# SUP_2_5_FMC.net
KiCad netlist of a schematic drawn in Altium Designer
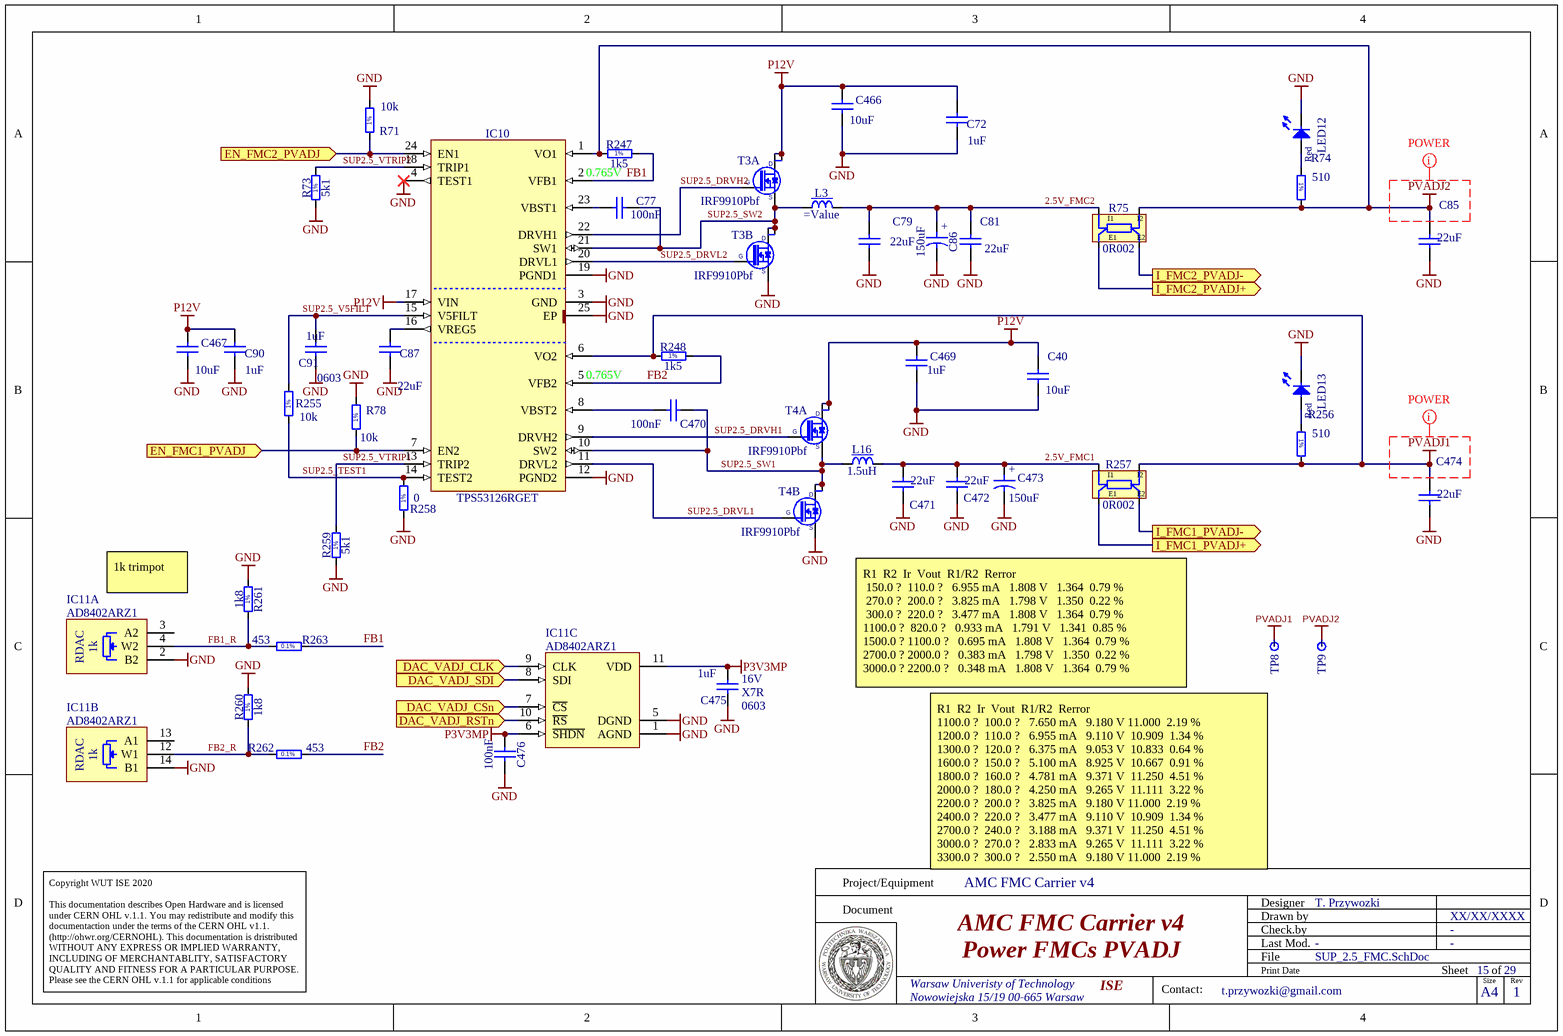
[diagram p0: SUP_2.5_FMC.SchDoc]

(export (version "E")
  (design (tool "Eeschema 10.0.6"))
  (components
    (comp (ref "C40")
      (value "10uF")
      (footprint "CAPC2012X135N")
      (description "Non-polarised capacitor")
      (fields
        (field (name "PART NUMBER") "CC0805_10UF_16V_10%_X5R")
        (field (name "VOLTAGE") "16V")
        (field (name "AUTHOR") "CERN DEM JLC")
      )
      (libsource (lib "Capacitors") (part "Capacitor - non polarized"))
    )
    (comp (ref "C72")
      (value "1uF")
      (footprint "CAPC1608X87N")
      (description "Non-polarised capacitor")
      (fields
        (field (name "PART NUMBER") "CC0603_1UF_16V_10%_X7R")
        (field (name "VOLTAGE") "16V")
        (field (name "AUTHOR") "CERN DEM JLC")
      )
      (libsource (lib "Capacitors") (part "Capacitor - non polarized"))
    )
    (comp (ref "C77")
      (value "100nF")
      (footprint "CAPC1005X55N")
      (description "Non-polarised capacitor")
      (fields
        (field (name "PART NUMBER") "CC0402_100NF_16V_10%_X7R")
        (field (name "VOLTAGE") "16V")
        (field (name "AUTHOR") "CERN DEM JLC")
      )
      (libsource (lib "Capacitors") (part "Capacitor - non polarized"))
    )
    (comp (ref "C79")
      (value "22uF")
      (footprint "CAPC3216X180N")
      (description "Non-polarised capacitor")
      (fields
        (field (name "PART NUMBER") "CC1206_22UF_10V_10%_X7R")
        (field (name "VOLTAGE") "10V")
        (field (name "AUTHOR") "CERN DEM JLC")
      )
      (libsource (lib "Capacitors") (part "Capacitor - non polarized"))
    )
    (comp (ref "C81")
      (value "22uF")
      (footprint "CAPC3216X180N")
      (description "Non-polarised capacitor")
      (fields
        (field (name "PART NUMBER") "CC1206_22UF_10V_10%_X7R")
        (field (name "VOLTAGE") "10V")
        (field (name "AUTHOR") "CERN DEM JLC")
      )
      (libsource (lib "Capacitors") (part "Capacitor - non polarized"))
    )
    (comp (ref "C85")
      (value "22uF")
      (footprint "CAPC3216X180N")
      (description "Non-polarised capacitor")
      (fields
        (field (name "PART NUMBER") "CC1206_22UF_10V_10%_X7R")
        (field (name "VOLTAGE") "10V")
        (field (name "AUTHOR") "CERN DEM JLC")
      )
      (libsource (lib "Capacitors") (part "Capacitor - non polarized"))
    )
    (comp (ref "C86")
      (value "150uF")
      (footprint "CAPMP7343X200N")
      (description "Polarised capacitor")
      (fields
        (field (name "PART NUMBER") "CAEM7343-20_150UF_4V_20%_LESR0016")
        (field (name "VOLTAGE") "4V")
        (field (name "AUTHOR") "CERN DEM JLC")
      )
      (libsource (lib "Capacitors") (part "Capacitor - polarized"))
    )
    (comp (ref "C87")
      (value "22uF")
      (footprint "CAPC3216X180N")
      (description "Non-polarised capacitor")
      (fields
        (field (name "PART NUMBER") "CC1206_22UF_10V_10%_X7R")
        (field (name "VOLTAGE") "10V")
        (field (name "AUTHOR") "CERN DEM JLC")
      )
      (libsource (lib "Capacitors") (part "Capacitor - non polarized"))
    )
    (comp (ref "C90")
      (value "1uF")
      (footprint "CAPC1608X87N")
      (description "Non-polarised capacitor")
      (fields
        (field (name "PART NUMBER") "CC0603_1UF_16V_10%_X7R")
        (field (name "VOLTAGE") "16V")
        (field (name "AUTHOR") "CERN DEM JLC")
      )
      (libsource (lib "Capacitors") (part "Capacitor - non polarized"))
    )
    (comp (ref "C91")
      (value "1uF")
      (footprint "CAPC1608X87N")
      (description "Non-polarised capacitor")
      (fields
        (field (name "PART NUMBER") "CC0603_1UF_16V_10%_X7R")
        (field (name "VOLTAGE") "16V")
        (field (name "CASE") "0603")
        (field (name "AUTHOR") "CERN DEM JLC")
      )
      (libsource (lib "Capacitors") (part "Capacitor - non polarized"))
    )
    (comp (ref "C466")
      (value "10uF")
      (footprint "CAPC2012X135N")
      (description "Non-polarised capacitor")
      (fields
        (field (name "PART NUMBER") "CC0805_10UF_16V_10%_X5R")
        (field (name "VOLTAGE") "16V")
        (field (name "AUTHOR") "CERN DEM JLC")
      )
      (libsource (lib "Capacitors") (part "Capacitor - non polarized"))
    )
    (comp (ref "C467")
      (value "10uF")
      (footprint "CAPC2012X135N")
      (description "Non-polarised capacitor")
      (fields
        (field (name "PART NUMBER") "CC0805_10UF_16V_10%_X5R")
        (field (name "VOLTAGE") "16V")
        (field (name "AUTHOR") "CERN DEM JLC")
      )
      (libsource (lib "Capacitors") (part "Capacitor - non polarized"))
    )
    (comp (ref "C469")
      (value "1uF")
      (footprint "CAPC1608X87N")
      (description "Non-polarised capacitor")
      (fields
        (field (name "PART NUMBER") "CC0603_1UF_16V_10%_X7R")
        (field (name "VOLTAGE") "16V")
        (field (name "AUTHOR") "CERN DEM JLC")
      )
      (libsource (lib "Capacitors") (part "Capacitor - non polarized"))
    )
    (comp (ref "C470")
      (value "100nF")
      (footprint "CAPC1005X55N")
      (description "Non-polarised capacitor")
      (fields
        (field (name "PART NUMBER") "CC0402_100NF_16V_10%_X7R")
        (field (name "VOLTAGE") "16V")
        (field (name "AUTHOR") "CERN DEM JLC")
      )
      (libsource (lib "Capacitors") (part "Capacitor - non polarized"))
    )
    (comp (ref "C471")
      (value "22uF")
      (footprint "CAPC3216X180N")
      (description "Non-polarised capacitor")
      (fields
        (field (name "PART NUMBER") "CC1206_22UF_10V_10%_X7R")
        (field (name "VOLTAGE") "10V")
        (field (name "AUTHOR") "CERN DEM JLC")
      )
      (libsource (lib "Capacitors") (part "Capacitor - non polarized"))
    )
    (comp (ref "C472")
      (value "22uF")
      (footprint "CAPC3216X180N")
      (description "Non-polarised capacitor")
      (fields
        (field (name "PART NUMBER") "CC1206_22UF_10V_10%_X7R")
        (field (name "VOLTAGE") "10V")
        (field (name "AUTHOR") "CERN DEM JLC")
      )
      (libsource (lib "Capacitors") (part "Capacitor - non polarized"))
    )
    (comp (ref "C473")
      (value "150uF")
      (footprint "CAPMP7343X200N")
      (description "Polarised capacitor")
      (fields
        (field (name "PART NUMBER") "CAEM7343-20_150UF_4V_20%_LESR0016")
        (field (name "VOLTAGE") "4V")
        (field (name "AUTHOR") "CERN DEM JLC")
      )
      (libsource (lib "Capacitors") (part "Capacitor - polarized"))
    )
    (comp (ref "C474")
      (value "22uF")
      (footprint "CAPC3216X180N")
      (description "Non-polarised capacitor")
      (fields
        (field (name "PART NUMBER") "CC1206_22UF_10V_10%_X7R")
        (field (name "VOLTAGE") "10V")
        (field (name "AUTHOR") "CERN DEM JLC")
      )
      (libsource (lib "Capacitors") (part "Capacitor - non polarized"))
    )
    (comp (ref "C475")
      (value "1uF")
      (footprint "CAPC1608X87N")
      (description "Non-polarised capacitor")
      (fields
        (field (name "PART NUMBER") "CC0603_1UF_16V_10%_X7R")
        (field (name "VOLTAGE") "16V")
        (field (name "TC") "X7R")
        (field (name "TOLERANCE") "±10%")
        (field (name "CASE") "0603")
        (field (name "AUTHOR") "CERN DEM JLC")
      )
      (libsource (lib "Capacitors") (part "Capacitor - non polarized"))
    )
    (comp (ref "C476")
      (value "100nF")
      (footprint "CAPC0603X33N")
      (description "Non-polarised capacitor")
      (fields
        (field (name "PART NUMBER") "CC0201_100NF_6.3V_10%_X5R")
        (field (name "VOLTAGE") "6.3V")
        (field (name "AUTHOR") "CERN DEM JLC")
      )
      (libsource (lib "Capacitors") (part "Capacitor - non polarized"))
    )
    (comp (ref "IC10")
      (value "TPS53126RGET")
      (footprint "QFN50P400X400X100-25N-S255")
      (description "Dual Synchronous Step-Down Controller For Low Voltage Power Rails")
      (fields (field (name "MANUFACTURER") "TEXAS INSTRUMENTS") (field (name "AUTHOR") "CERN DEM JLC"))
      (libsource (lib "ICs And Semiconductors") (part "TPS53126RGET"))
    )
    (comp (ref "IC11")
      (value "AD8402ARZ1")
      (footprint "SOIC127P600X175-14N")
      (description "2-Channel 1k Digital Potentiometer")
      (fields (field (name "MANUFACTURER") "ANALOG DEVICES") (field (name "AUTHOR") "CERN DEM JLC"))
      (libsource (lib "ICs And Semiconductors") (part "AD8402ARZ1"))
    )
    (comp (ref "L3")
      (value "~")
      (description "Inductor With Core")
      (libsource (lib "altium-import") (part "root_0_Inductor With Magnetic core_"))
    )
    (comp (ref "L16")
      (value "1.5uH")
      (footprint "IND_TDK_SPM6530")
      (description "Inductor With Core")
      (fields
        (field (name "PART NUMBER") "IND_1.5UH_20%_TDK_SPM6530")
        (field (name "POWER") "11A")
        (field (name "AUTHOR") "CERN DEM MR")
      )
      (libsource (lib "Inductors & Transformers") (part "Inductor With Magnetic core"))
    )
    (comp (ref "LED12")
      (value "Red")
      (footprint "LED_KINGBRIGHT_KPH-1608SURCK")
      (description "LED Red 1C 2A")
      (fields
        (field (name "PART NUMBER") "LED_KINGBRIGHT_KPH-1608SURCK")
        (field (name "MANUFACTURER") "KINGBRIGHT")
        (field (name "AUTHOR") "CERN DEM JLC")
      )
      (libsource (lib "ICs And Semiconductors") (part "LED Red 1C 2A"))
    )
    (comp (ref "LED13")
      (value "Red")
      (footprint "LED_KINGBRIGHT_KPH-1608SURCK")
      (description "LED Red 1C 2A")
      (fields
        (field (name "PART NUMBER") "LED_KINGBRIGHT_KPH-1608SURCK")
        (field (name "MANUFACTURER") "KINGBRIGHT")
        (field (name "AUTHOR") "CERN DEM JLC")
      )
      (libsource (lib "ICs And Semiconductors") (part "LED Red 1C 2A"))
    )
    (comp (ref "R71")
      (value "10k")
      (footprint "RESC1005X40N")
      (description "Resistor - 1%")
      (fields
        (field (name "PART NUMBER") "R0402_10K_1%_0.0625W_100PPM")
        (field (name "POWER") "0.0625W")
        (field (name "AUTHOR") "CERN DEM JLC")
      )
      (libsource (lib "Resistors") (part "Resistor - 1%"))
    )
    (comp (ref "R73")
      (value "5k1")
      (footprint "RESC1608X55N")
      (description "Resistor - 1%")
      (fields
        (field (name "PART NUMBER") "R0603_5K1_1%_0.1W_100PPM")
        (field (name "POWER") "0.1W")
        (field (name "AUTHOR") "CERN DEM JLC")
      )
      (libsource (lib "Resistors") (part "Resistor - 1%"))
    )
    (comp (ref "R74")
      (value "510")
      (footprint "RESC1005X40N")
      (description "Resistor - 1%")
      (fields
        (field (name "PART NUMBER") "R0402_510R_1%_0.0625W_100PPM")
        (field (name "POWER") "0.0625W")
        (field (name "AUTHOR") "CERN DEM JLC")
      )
      (libsource (lib "Resistors") (part "Resistor - 1%"))
    )
    (comp (ref "R75")
      (value "0R002")
      (footprint "RES_VISHAY_WSK2512_0R005-0R2")
      (description "Power and Current Sensing Resistor")
      (fields
        (field (name "PART NUMBER") "R2512_0R002_1%_1W_35PPM_VISHAY_WSK")
        (field (name "POWER") "1W")
        (field (name "AUTHOR") "CERN DEM MR")
      )
      (libsource (lib "Resistors") (part "Current Sense Resistor"))
    )
    (comp (ref "R78")
      (value "10k")
      (footprint "RESC1005X40N")
      (description "Resistor - 1%")
      (fields
        (field (name "PART NUMBER") "R0402_10K_1%_0.0625W_100PPM")
        (field (name "POWER") "0.0625W")
        (field (name "AUTHOR") "CERN DEM JLC")
      )
      (libsource (lib "Resistors") (part "Resistor - 1%"))
    )
    (comp (ref "R247")
      (value "1k5")
      (footprint "RESC1608X55N")
      (description "Resistor - 1%")
      (fields
        (field (name "PART NUMBER") "R0603_1K5_1%_0.1W_100PPM")
        (field (name "POWER") "0.1W")
        (field (name "AUTHOR") "CERN DEM JLC")
      )
      (libsource (lib "Resistors") (part "Resistor - 1%"))
    )
    (comp (ref "R248")
      (value "1k5")
      (footprint "RESC1608X55N")
      (description "Resistor - 1%")
      (fields
        (field (name "PART NUMBER") "R0603_1K5_1%_0.1W_100PPM")
        (field (name "POWER") "0.1W")
        (field (name "AUTHOR") "CERN DEM JLC")
      )
      (libsource (lib "Resistors") (part "Resistor - 1%"))
    )
    (comp (ref "R255")
      (value "10k")
      (footprint "RESC1005X40N")
      (description "Resistor - 1%")
      (fields
        (field (name "PART NUMBER") "R0402_10K_1%_0.0625W_100PPM")
        (field (name "POWER") "0.0625W")
        (field (name "AUTHOR") "CERN DEM JLC")
      )
      (libsource (lib "Resistors") (part "Resistor - 1%"))
    )
    (comp (ref "R256")
      (value "510")
      (footprint "RESC1005X40N")
      (description "Resistor - 1%")
      (fields
        (field (name "PART NUMBER") "R0402_510R_1%_0.0625W_100PPM")
        (field (name "POWER") "0.0625W")
        (field (name "AUTHOR") "CERN DEM JLC")
      )
      (libsource (lib "Resistors") (part "Resistor - 1%"))
    )
    (comp (ref "R257")
      (value "0R002")
      (footprint "RES_VISHAY_WSK2512_0R005-0R2")
      (description "Power and Current Sensing Resistor")
      (fields
        (field (name "PART NUMBER") "R2512_0R002_1%_1W_35PPM_VISHAY_WSK")
        (field (name "POWER") "1W")
        (field (name "AUTHOR") "CERN DEM MR")
      )
      (libsource (lib "Resistors") (part "Current Sense Resistor"))
    )
    (comp (ref "R258")
      (value "0")
      (footprint "RESC1005X40N")
      (description "Resistor - 1%")
      (fields
        (field (name "PART NUMBER") "R0402_0R_JUMPER")
        (field (name "MANUFACTURER") "GENERIC")
        (field (name "AUTHOR") "CERN DEM JLC")
      )
      (libsource (lib "Resistors") (part "Resistor - 1%"))
    )
    (comp (ref "R259")
      (value "5k1")
      (footprint "RESC1608X55N")
      (description "Resistor - 1%")
      (fields
        (field (name "PART NUMBER") "R0603_5K1_1%_0.1W_100PPM")
        (field (name "POWER") "0.1W")
        (field (name "AUTHOR") "CERN DEM JLC")
      )
      (libsource (lib "Resistors") (part "Resistor - 1%"))
    )
    (comp (ref "R260")
      (value "1k8")
      (footprint "RESC1608X55N")
      (description "Resistor - 1%")
      (fields
        (field (name "PART NUMBER") "R0603_910R_1%_0.1W_100PPM")
        (field (name "POWER") "0.1W")
        (field (name "AUTHOR") "CERN DEM JLC")
      )
      (libsource (lib "Resistors") (part "Resistor - 1%"))
    )
    (comp (ref "R261")
      (value "1k8")
      (footprint "RESC1608X55N")
      (description "Resistor - 1%")
      (fields
        (field (name "PART NUMBER") "R0603_910R_1%_0.1W_100PPM")
        (field (name "POWER") "0.1W")
        (field (name "AUTHOR") "CERN DEM JLC")
      )
      (libsource (lib "Resistors") (part "Resistor - 1%"))
    )
    (comp (ref "R262")
      (value "453")
      (footprint "RESC1608X55N")
      (description "Resistor - 0.1%")
      (fields
        (field (name "PART NUMBER") "R0603_453R_0.1%_0.063W_10PPM")
        (field (name "POWER") "0.063W")
        (field (name "AUTHOR") "CERN DEM JLC")
      )
      (libsource (lib "Resistors") (part "Resistor - 0.1%"))
    )
    (comp (ref "R263")
      (value "453")
      (footprint "RESC1608X55N")
      (description "Resistor - 0.1%")
      (fields
        (field (name "PART NUMBER") "R0603_453R_0.1%_0.063W_10PPM")
        (field (name "POWER") "0.063W")
        (field (name "AUTHOR") "CERN DEM JLC")
      )
      (libsource (lib "Resistors") (part "Resistor - 0.1%"))
    )
    (comp (ref "T3")
      (value "IRF9910Pbf")
      (footprint "SOIC127P600X175-8N")
      (description "Dual SO-8 MOSFET For POL Cconverter")
      (fields (field (name "MANUFACTURER") "INTERNATIONAL RECTIFIER") (field (name "AUTHOR") "CERN DEM JLC"))
      (libsource (lib "ICs And Semiconductors") (part "IRF9910"))
    )
    (comp (ref "T4")
      (value "IRF9910Pbf")
      (footprint "SOIC127P600X175-8N")
      (description "Dual SO-8 MOSFET For POL Cconverter")
      (fields (field (name "MANUFACTURER") "INTERNATIONAL RECTIFIER") (field (name "AUTHOR") "CERN DEM JLC"))
      (libsource (lib "ICs And Semiconductors") (part "IRF9910"))
    )
    (comp (ref "TP8")
      (value "Test Point")
      (footprint "TPS127")
      (fields (field (name "PART NUMBER") "SMD_PAD_1.27X1.27MM") (field (name "AUTHOR") "CERN DEM JLC"))
      (libsource (lib "Eletro-mechanical") (part "Test Point"))
    )
    (comp (ref "TP9")
      (value "Test Point")
      (footprint "TPS127")
      (fields (field (name "PART NUMBER") "SMD_PAD_1.27X1.27MM") (field (name "AUTHOR") "CERN DEM JLC"))
      (libsource (lib "Eletro-mechanical") (part "Test Point"))
    )
  )
  (nets
    (net (code "1") (name "/2.5V_FMC1") (class "Default")
      (node (ref "C471") (pin "1") (pinfunction "1_1") (pintype "passive"))
      (node (ref "C472") (pin "1") (pinfunction "1_1") (pintype "passive"))
      (node (ref "C473") (pin "1") (pinfunction "1_1") (pintype "passive"))
      (node (ref "L16") (pin "2") (pinfunction "2_2") (pintype "passive"))
      (node (ref "R257") (pin "I1") (pinfunction "I1_I1") (pintype "passive"))
    )
    (net (code "2") (name "/2.5V_FMC2") (class "Default")
      (node (ref "C79") (pin "1") (pinfunction "1_1") (pintype "passive"))
      (node (ref "C81") (pin "1") (pinfunction "1_1") (pintype "passive"))
      (node (ref "C86") (pin "1") (pinfunction "1_1") (pintype "passive"))
      (node (ref "L3") (pin "2") (pinfunction "2_2") (pintype "passive"))
      (node (ref "R75") (pin "I1") (pinfunction "I1_I1") (pintype "passive"))
    )
    (net (code "3") (name "/DAC_VADJ_CLK") (class "Default")
      (node (ref "IC11") (pin "9") (pinfunction "CLK_9") (pintype "input"))
    )
    (net (code "4") (name "/DAC_VADJ_CSn") (class "Default")
      (node (ref "IC11") (pin "7") (pinfunction "~{CS}_7") (pintype "input"))
    )
    (net (code "5") (name "/DAC_VADJ_RSTn") (class "Default")
      (node (ref "IC11") (pin "10") (pinfunction "~{RS}_10") (pintype "input"))
    )
    (net (code "6") (name "/DAC_VADJ_SDI") (class "Default")
      (node (ref "IC11") (pin "8") (pinfunction "SDI_8") (pintype "input"))
    )
    (net (code "7") (name "/EN_FMC1_PVADJ") (class "Default")
      (node (ref "IC10") (pin "7") (pinfunction "EN2_7") (pintype "input"))
      (node (ref "R78") (pin "1") (pinfunction "1_1") (pintype "passive"))
    )
    (net (code "8") (name "/EN_FMC2_PVADJ") (class "Default")
      (node (ref "IC10") (pin "24") (pinfunction "EN1_24") (pintype "input"))
      (node (ref "R71") (pin "1") (pinfunction "1_1") (pintype "passive"))
    )
    (net (code "9") (name "/FB1") (class "Default")
      (node (ref "IC10") (pin "2") (pinfunction "VFB1_2") (pintype "input"))
      (node (ref "R247") (pin "2") (pinfunction "2_2") (pintype "passive"))
      (node (ref "R263") (pin "1") (pinfunction "1_1") (pintype "passive"))
    )
    (net (code "10") (name "/FB1_R") (class "Default")
      (node (ref "IC11") (pin "4") (pinfunction "W2_4") (pintype "passive"))
      (node (ref "R261") (pin "1") (pinfunction "1_1") (pintype "passive"))
      (node (ref "R263") (pin "2") (pinfunction "2_2") (pintype "passive"))
    )
    (net (code "11") (name "/FB2") (class "Default")
      (node (ref "IC10") (pin "5") (pinfunction "VFB2_5") (pintype "input"))
      (node (ref "R248") (pin "2") (pinfunction "2_2") (pintype "passive"))
      (node (ref "R262") (pin "2") (pinfunction "2_2") (pintype "passive"))
    )
    (net (code "12") (name "/FB2_R") (class "Default")
      (node (ref "IC11") (pin "12") (pinfunction "W1_12") (pintype "passive"))
      (node (ref "R260") (pin "1") (pinfunction "1_1") (pintype "passive"))
      (node (ref "R262") (pin "1") (pinfunction "1_1") (pintype "passive"))
    )
    (net (code "13") (name "/I_FMC1_PVADJ+") (class "Default")
      (node (ref "R257") (pin "E1") (pinfunction "E1_E1") (pintype "passive"))
    )
    (net (code "14") (name "/I_FMC1_PVADJ-") (class "Default")
      (node (ref "R257") (pin "E2") (pinfunction "E2_E2") (pintype "passive"))
    )
    (net (code "15") (name "/I_FMC2_PVADJ+") (class "Default")
      (node (ref "R75") (pin "E1") (pinfunction "E1_E1") (pintype "passive"))
    )
    (net (code "16") (name "/I_FMC2_PVADJ-") (class "Default")
      (node (ref "R75") (pin "E2") (pinfunction "E2_E2") (pintype "passive"))
    )
    (net (code "17") (name "/SUP2.5_DRVH1") (class "Default")
      (node (ref "IC10") (pin "9") (pinfunction "DRVH2_9") (pintype "output"))
      (node (ref "T4") (pin "4") (pinfunction "G_4") (pintype "passive"))
    )
    (net (code "18") (name "/SUP2.5_DRVH2") (class "Default")
      (node (ref "IC10") (pin "22") (pinfunction "DRVH1_22") (pintype "output"))
      (node (ref "T3") (pin "4") (pinfunction "G_4") (pintype "passive"))
    )
    (net (code "19") (name "/SUP2.5_DRVL1") (class "Default")
      (node (ref "IC10") (pin "11") (pinfunction "DRVL2_11") (pintype "output"))
      (node (ref "T4") (pin "2") (pinfunction "G_2") (pintype "passive"))
    )
    (net (code "20") (name "/SUP2.5_DRVL2") (class "Default")
      (node (ref "IC10") (pin "20") (pinfunction "DRVL1_20") (pintype "output"))
      (node (ref "T3") (pin "2") (pinfunction "G_2") (pintype "passive"))
    )
    (net (code "21") (name "/SUP2.5_SW1") (class "Default")
      (node (ref "C470") (pin "1") (pinfunction "1_1") (pintype "passive"))
      (node (ref "IC10") (pin "10") (pinfunction "SW2_10") (pintype "bidirectional"))
      (node (ref "L16") (pin "1") (pinfunction "1_1") (pintype "passive"))
      (node (ref "T4") (pin "3") (pinfunction "S_3") (pintype "passive"))
      (node (ref "T4") (pin "7") (pinfunction "D_7") (pintype "passive"))
      (node (ref "T4") (pin "8") (pinfunction "D_8") (pintype "passive"))
    )
    (net (code "22") (name "/SUP2.5_SW2") (class "Default")
      (node (ref "C77") (pin "1") (pinfunction "1_1") (pintype "passive"))
      (node (ref "IC10") (pin "21") (pinfunction "SW1_21") (pintype "bidirectional"))
      (node (ref "L3") (pin "1") (pinfunction "1_1") (pintype "passive"))
      (node (ref "T3") (pin "3") (pinfunction "S_3") (pintype "passive"))
      (node (ref "T3") (pin "7") (pinfunction "D_7") (pintype "passive"))
      (node (ref "T3") (pin "8") (pinfunction "D_8") (pintype "passive"))
    )
    (net (code "23") (name "/SUP2.5_TEST1") (class "Default")
      (node (ref "IC10") (pin "14") (pinfunction "TEST2_14") (pintype "input"))
      (node (ref "R255") (pin "1") (pinfunction "1_1") (pintype "passive"))
      (node (ref "R258") (pin "2") (pinfunction "2_2") (pintype "passive"))
    )
    (net (code "24") (name "/SUP2.5_V5FILT") (class "Default")
      (node (ref "C91") (pin "2") (pinfunction "2_2") (pintype "passive"))
      (node (ref "IC10") (pin "15") (pinfunction "V5FILT_15") (pintype "input"))
      (node (ref "R255") (pin "2") (pinfunction "2_2") (pintype "passive"))
    )
    (net (code "25") (name "/SUP2.5_VTRIP1") (class "Default")
      (node (ref "IC10") (pin "13") (pinfunction "TRIP2_13") (pintype "input"))
      (node (ref "R259") (pin "2") (pinfunction "2_2") (pintype "passive"))
    )
    (net (code "26") (name "/SUP2.5_VTRIP2") (class "Default")
      (node (ref "IC10") (pin "18") (pinfunction "TRIP1_18") (pintype "input"))
      (node (ref "R73") (pin "2") (pinfunction "2_2") (pintype "passive"))
    )
    (net (code "27") (name "GND") (class "Default")
      (node (ref "C40") (pin "1") (pinfunction "1_1") (pintype "passive"))
      (node (ref "C466") (pin "1") (pinfunction "1_1") (pintype "passive"))
      (node (ref "C467") (pin "1") (pinfunction "1_1") (pintype "passive"))
      (node (ref "C469") (pin "1") (pinfunction "1_1") (pintype "passive"))
      (node (ref "C471") (pin "2") (pinfunction "2_2") (pintype "passive"))
      (node (ref "C472") (pin "2") (pinfunction "2_2") (pintype "passive"))
      (node (ref "C473") (pin "2") (pinfunction "2_2") (pintype "passive"))
      (node (ref "C474") (pin "2") (pinfunction "2_2") (pintype "passive"))
      (node (ref "C475") (pin "1") (pinfunction "1_1") (pintype "passive"))
      (node (ref "C476") (pin "2") (pinfunction "2_2") (pintype "passive"))
      (node (ref "C72") (pin "1") (pinfunction "1_1") (pintype "passive"))
      (node (ref "C79") (pin "2") (pinfunction "2_2") (pintype "passive"))
      (node (ref "C81") (pin "2") (pinfunction "2_2") (pintype "passive"))
      (node (ref "C85") (pin "2") (pinfunction "2_2") (pintype "passive"))
      (node (ref "C86") (pin "2") (pinfunction "2_2") (pintype "passive"))
      (node (ref "C87") (pin "1") (pinfunction "1_1") (pintype "passive"))
      (node (ref "C90") (pin "1") (pinfunction "1_1") (pintype "passive"))
      (node (ref "C91") (pin "1") (pinfunction "1_1") (pintype "passive"))
      (node (ref "IC10") (pin "12") (pinfunction "PGND2_12") (pintype "power_in"))
      (node (ref "IC10") (pin "19") (pinfunction "PGND1_19") (pintype "power_in"))
      (node (ref "IC10") (pin "25") (pinfunction "EP_25") (pintype "power_in"))
      (node (ref "IC10") (pin "3") (pinfunction "GND_3") (pintype "power_in"))
      (node (ref "IC10") (pin "4") (pinfunction "TEST1_4") (pintype "output"))
      (node (ref "IC11") (pin "1") (pinfunction "AGND_1") (pintype "power_in"))
      (node (ref "IC11") (pin "14") (pinfunction "B1_14") (pintype "passive"))
      (node (ref "IC11") (pin "2") (pinfunction "B2_2") (pintype "passive"))
      (node (ref "IC11") (pin "5") (pinfunction "DGND_5") (pintype "power_in"))
      (node (ref "LED12") (pin "1") (pinfunction "C_1") (pintype "passive"))
      (node (ref "LED13") (pin "1") (pinfunction "C_1") (pintype "passive"))
      (node (ref "R258") (pin "1") (pinfunction "1_1") (pintype "passive"))
      (node (ref "R259") (pin "1") (pinfunction "1_1") (pintype "passive"))
      (node (ref "R260") (pin "2") (pinfunction "2_2") (pintype "passive"))
      (node (ref "R261") (pin "2") (pinfunction "2_2") (pintype "passive"))
      (node (ref "R71") (pin "2") (pinfunction "2_2") (pintype "passive"))
      (node (ref "R73") (pin "1") (pinfunction "1_1") (pintype "passive"))
      (node (ref "R78") (pin "2") (pinfunction "2_2") (pintype "passive"))
      (node (ref "T3") (pin "1") (pinfunction "S_1") (pintype "passive"))
      (node (ref "T4") (pin "1") (pinfunction "S_1") (pintype "passive"))
    )
    (net (code "28") (name "Net-(IC10-VBST1)") (class "Default")
      (node (ref "C77") (pin "2") (pinfunction "2_2") (pintype "passive"))
      (node (ref "IC10") (pin "23") (pinfunction "VBST1_23") (pintype "input"))
    )
    (net (code "29") (name "Net-(IC10-VBST2)") (class "Default")
      (node (ref "C470") (pin "2") (pinfunction "2_2") (pintype "passive"))
      (node (ref "IC10") (pin "8") (pinfunction "VBST2_8") (pintype "input"))
    )
    (net (code "30") (name "Net-(IC10-VREG5)") (class "Default")
      (node (ref "C87") (pin "2") (pinfunction "2_2") (pintype "passive"))
      (node (ref "IC10") (pin "16") (pinfunction "VREG5_16") (pintype "output"))
    )
    (net (code "31") (name "Net-(LED12-A)") (class "Default")
      (node (ref "LED12") (pin "2") (pinfunction "A_2") (pintype "passive"))
      (node (ref "R74") (pin "1") (pinfunction "1_1") (pintype "passive"))
    )
    (net (code "32") (name "Net-(LED13-A)") (class "Default")
      (node (ref "LED13") (pin "2") (pinfunction "A_2") (pintype "passive"))
      (node (ref "R256") (pin "1") (pinfunction "1_1") (pintype "passive"))
    )
    (net (code "33") (name "P3V3MP") (class "Default")
      (node (ref "C475") (pin "2") (pinfunction "2_2") (pintype "passive"))
      (node (ref "C476") (pin "1") (pinfunction "1_1") (pintype "passive"))
      (node (ref "IC11") (pin "11") (pinfunction "VDD_11") (pintype "power_in"))
      (node (ref "IC11") (pin "6") (pinfunction "~{SHDN}_6") (pintype "input"))
    )
    (net (code "34") (name "P12V") (class "Default")
      (node (ref "C40") (pin "2") (pinfunction "2_2") (pintype "passive"))
      (node (ref "C466") (pin "2") (pinfunction "2_2") (pintype "passive"))
      (node (ref "C467") (pin "2") (pinfunction "2_2") (pintype "passive"))
      (node (ref "C469") (pin "2") (pinfunction "2_2") (pintype "passive"))
      (node (ref "C72") (pin "2") (pinfunction "2_2") (pintype "passive"))
      (node (ref "C90") (pin "2") (pinfunction "2_2") (pintype "passive"))
      (node (ref "IC10") (pin "17") (pinfunction "VIN_17") (pintype "input"))
      (node (ref "T3") (pin "5") (pinfunction "D_5") (pintype "passive"))
      (node (ref "T3") (pin "6") (pinfunction "D_6") (pintype "passive"))
      (node (ref "T4") (pin "5") (pinfunction "D_5") (pintype "passive"))
      (node (ref "T4") (pin "6") (pinfunction "D_6") (pintype "passive"))
    )
    (net (code "35") (name "PVADJ1") (class "Default")
      (node (ref "C474") (pin "1") (pinfunction "1_1") (pintype "passive"))
      (node (ref "IC10") (pin "6") (pinfunction "VO2_6") (pintype "input"))
      (node (ref "R248") (pin "1") (pinfunction "1_1") (pintype "passive"))
      (node (ref "R256") (pin "2") (pinfunction "2_2") (pintype "passive"))
      (node (ref "R257") (pin "I2") (pinfunction "I2_I2") (pintype "passive"))
      (node (ref "TP8") (pin "1") (pinfunction "1_1") (pintype "bidirectional"))
    )
    (net (code "36") (name "PVADJ2") (class "Default")
      (node (ref "C85") (pin "1") (pinfunction "1_1") (pintype "passive"))
      (node (ref "IC10") (pin "1") (pinfunction "VO1_1") (pintype "input"))
      (node (ref "R247") (pin "1") (pinfunction "1_1") (pintype "passive"))
      (node (ref "R74") (pin "2") (pinfunction "2_2") (pintype "passive"))
      (node (ref "R75") (pin "I2") (pinfunction "I2_I2") (pintype "passive"))
      (node (ref "TP9") (pin "1") (pinfunction "1_1") (pintype "bidirectional"))
    )
    (net (code "37") (name "unconnected-(IC11A-A2-Pad3)") (class "Default")
      (node (ref "IC11") (pin "3") (pinfunction "A2_3") (pintype "passive"))
    )
    (net (code "38") (name "unconnected-(IC11B-A1-Pad13)") (class "Default")
      (node (ref "IC11") (pin "13") (pinfunction "A1_13") (pintype "passive"))
    )
  )
)
